# bms.net
KiCad netlist of a schematic drawn in EAGLE
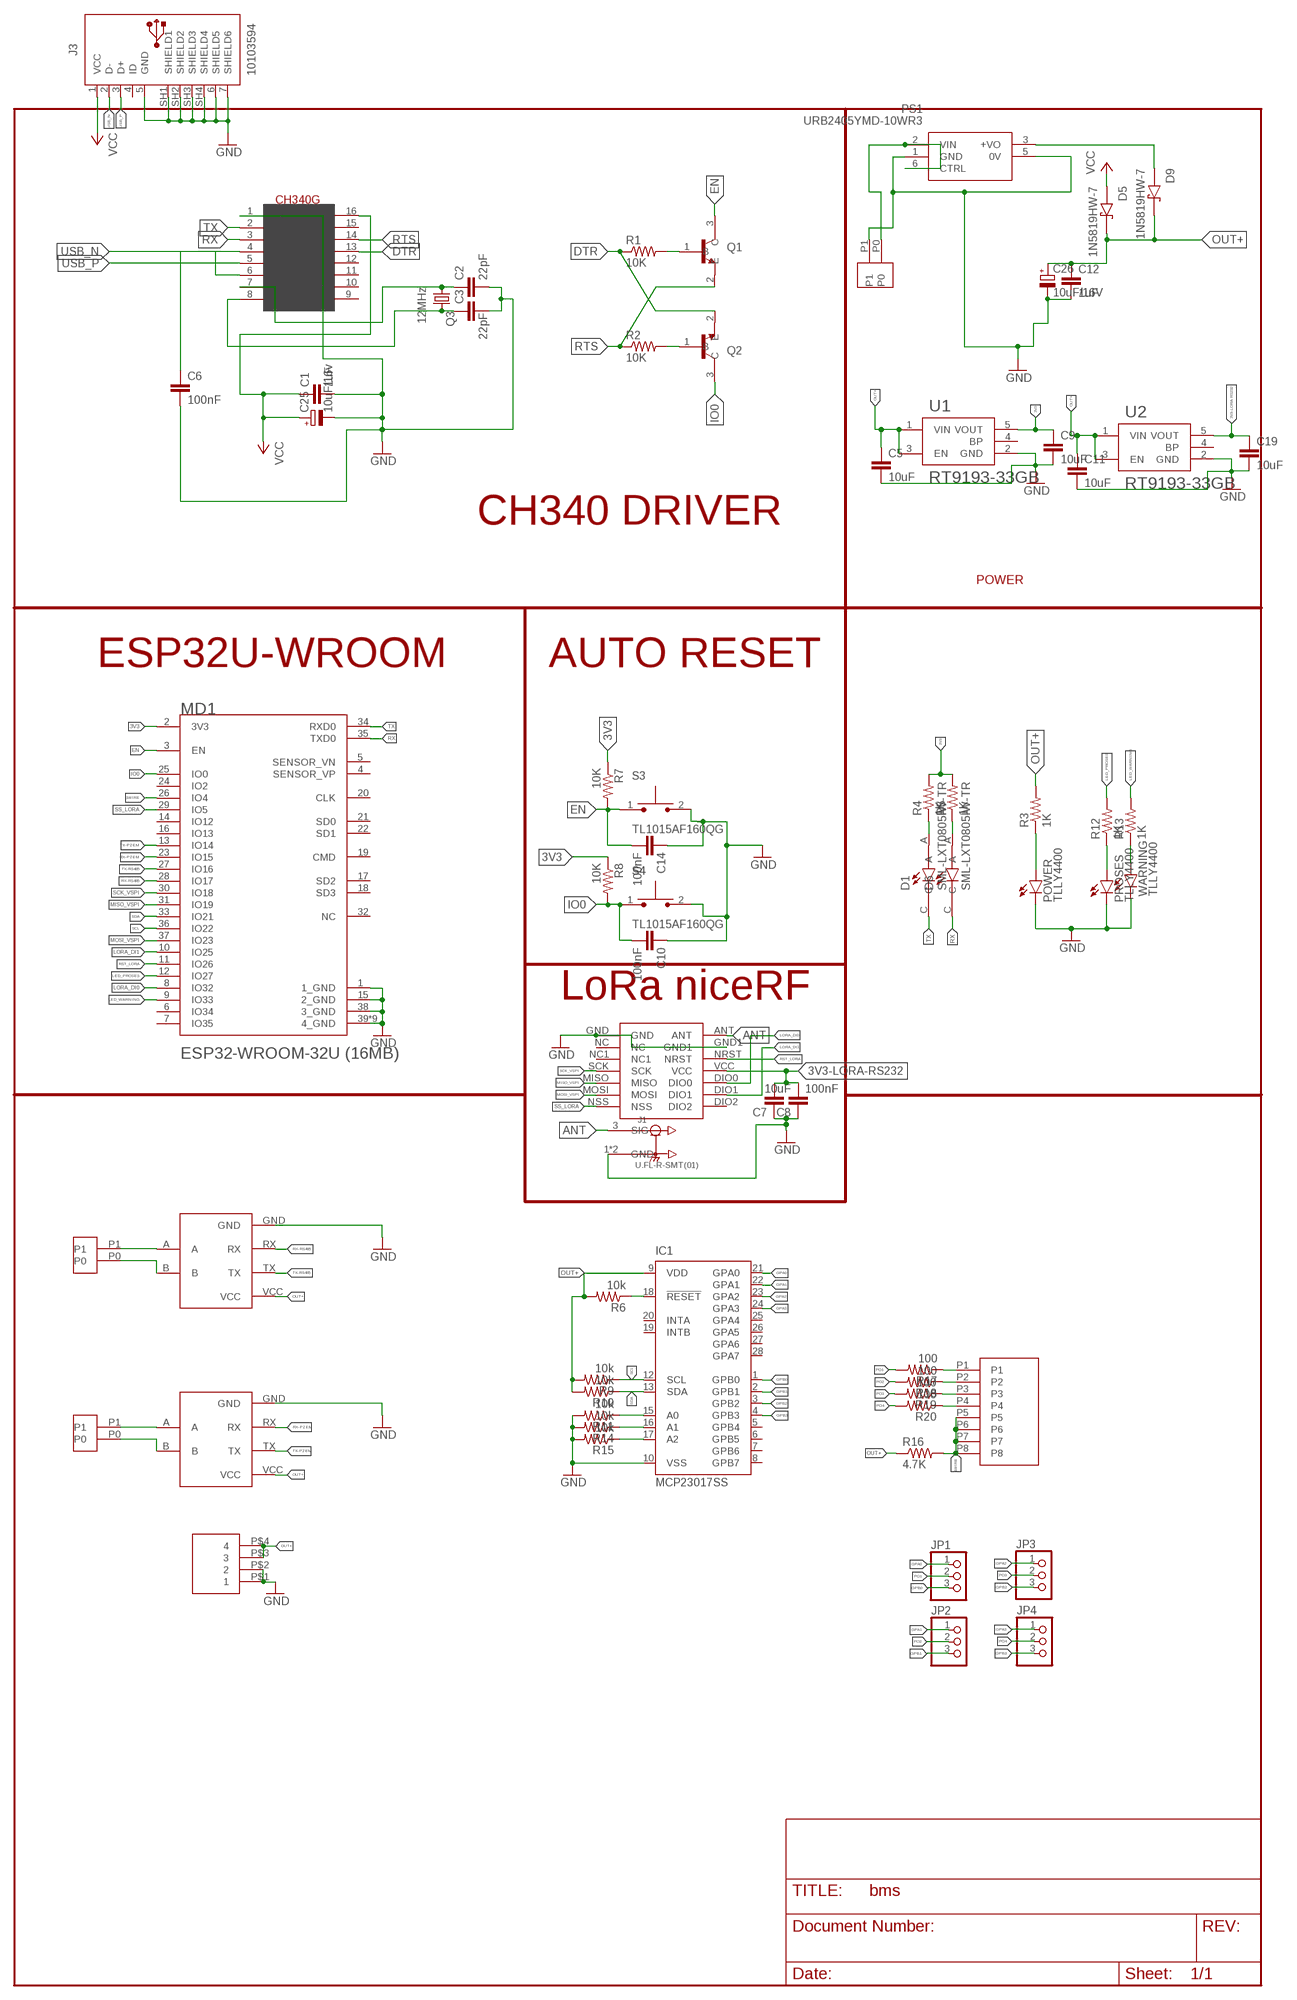
[diagram p0: schematic, sheet 1]

(export (version "E")
  (design (tool "Eeschema 10.0.6"))
  (components
    (comp (ref "C1")
      (value "1uF")
      (footprint "eagle-import:C0805K")
      (libsource (lib "eagle-import") (part "C-EUC0805K"))
    )
    (comp (ref "C2")
      (value "22pF")
      (footprint "eagle-import:C0805K")
      (libsource (lib "eagle-import") (part "C-EUC0805K"))
    )
    (comp (ref "C3")
      (value "22pF")
      (footprint "eagle-import:C0805K")
      (libsource (lib "eagle-import") (part "C-EUC0805K"))
    )
    (comp (ref "C5")
      (value "10uF")
      (footprint "eagle-import:C0805K")
      (libsource (lib "eagle-import") (part "C-EUC0805K"))
    )
    (comp (ref "C6")
      (value "100nF")
      (footprint "eagle-import:C0805K")
      (libsource (lib "eagle-import") (part "C-EUC0805K"))
    )
    (comp (ref "C7")
      (value "10uF")
      (footprint "eagle-import:C0805K")
      (libsource (lib "eagle-import") (part "C-EUC0805K"))
    )
    (comp (ref "C8")
      (value "100nF")
      (footprint "eagle-import:C0805K")
      (libsource (lib "eagle-import") (part "C-EUC0805K"))
    )
    (comp (ref "C9")
      (value "10uF")
      (footprint "eagle-import:C0805K")
      (libsource (lib "eagle-import") (part "C-EUC0805K"))
    )
    (comp (ref "C10")
      (value "100nF")
      (footprint "eagle-import:C0805K")
      (libsource (lib "eagle-import") (part "C-EUC0805K"))
    )
    (comp (ref "C11")
      (value "10uF")
      (footprint "eagle-import:C0805K")
      (libsource (lib "eagle-import") (part "C-EUC0805K"))
    )
    (comp (ref "C12")
      (value "1uF")
      (footprint "eagle-import:C0805K")
      (libsource (lib "eagle-import") (part "C-EUC0805K"))
    )
    (comp (ref "C14")
      (value "100nF")
      (footprint "eagle-import:C0805K")
      (libsource (lib "eagle-import") (part "C-EUC0805K"))
    )
    (comp (ref "C19")
      (value "10uF")
      (footprint "eagle-import:C0805K")
      (libsource (lib "eagle-import") (part "C-EUC0805K"))
    )
    (comp (ref "C25")
      (value "10uF/16v")
      (footprint "eagle-import:153CLV-0505")
      (libsource (lib "eagle-import") (part "CPOL-EU153CLV-0505"))
    )
    (comp (ref "C26")
      (value "10uF/16V")
      (footprint "eagle-import:153CLV-0505")
      (libsource (lib "eagle-import") (part "CPOL-EU153CLV-0505"))
    )
    (comp (ref "CONN2P-3.5PI1")
      (value "CONN2P-3.5PI")
      (footprint "eagle-import:CONN2P-3.5PI")
      (libsource (lib "eagle-import") (part "CONN2P-3.5PI"))
    )
    (comp (ref "CONN2P-3.5PI2")
      (value "CONN2P-3.5PI")
      (footprint "eagle-import:CONN2P-3.5PI")
      (libsource (lib "eagle-import") (part "CONN2P-3.5PI"))
    )
    (comp (ref "CONN2P-3.5PI3")
      (value "CONN2P-3.5PI")
      (footprint "eagle-import:CONN2P-3.5PI")
      (libsource (lib "eagle-import") (part "CONN2P-3.5PI"))
    )
    (comp (ref "CONN3.1")
      (value "CONN3.5")
      (footprint "eagle-import:CONN3.5")
      (libsource (lib "eagle-import") (part "CONN3.5"))
    )
    (comp (ref "D1")
      (value "SML-LXT0805IW-TR")
      (footprint "eagle-import:LEDC2012X120N")
      (fields (field (name "MF") "Lumex Opto/Components"))
      (libsource (lib "eagle-import") (part "SML-LXT0805IW-TR"))
    )
    (comp (ref "D5")
      (value "1N5819HW-7")
      (footprint "eagle-import:SOD3715X145N")
      (fields (field (name "MF") "Diodes Inc."))
      (libsource (lib "eagle-import") (part "1N5819HW-7"))
    )
    (comp (ref "D6")
      (value "SML-LXT0805IW-TR")
      (footprint "eagle-import:LEDC2012X120N")
      (fields (field (name "MF") "Lumex Opto/Components"))
      (libsource (lib "eagle-import") (part "SML-LXT0805IW-TR"))
    )
    (comp (ref "D9")
      (value "1N5819HW-7")
      (footprint "eagle-import:SOD3715X145N")
      (fields (field (name "MF") "Diodes Inc."))
      (libsource (lib "eagle-import") (part "1N5819HW-7"))
    )
    (comp (ref "HEADER-3.81-1")
      (value "HEADER-3.81-4")
      (footprint "eagle-import:HEADER-3.81-4")
      (libsource (lib "eagle-import") (part "HEADER-3.81-4"))
    )
    (comp (ref "IC1")
      (value "MCP23017SS")
      (footprint "eagle-import:SSOP28")
      (fields (field (name "MF") "MICROCHIP") (field (name "MPN") "MCP23017-E/SS"))
      (libsource (lib "eagle-import") (part "MCP23017SS"))
    )
    (comp (ref "J1")
      (value "U.FL-R-SMT(01)")
      (footprint "eagle-import:HRS_U.FL-R-SMT(01)")
      (fields (field (name "MF") "Hirose"))
      (libsource (lib "eagle-import") (part "U.FL-R-SMT(01)"))
    )
    (comp (ref "J3")
      (value "10103594")
      (footprint "eagle-import:10103594")
      (fields (field (name "MANUFACTURER") "Amphenol ICC (FCI)") (field (name "MPN") "10103594-0001LF"))
      (libsource (lib "eagle-import") (part "10103594"))
    )
    (comp (ref "JP1")
      (value "PINHD-1X3")
      (footprint "eagle-import:1X03")
      (libsource (lib "eagle-import") (part "PINHD-1X3"))
    )
    (comp (ref "JP2")
      (value "PINHD-1X3")
      (footprint "eagle-import:1X03")
      (libsource (lib "eagle-import") (part "PINHD-1X3"))
    )
    (comp (ref "JP3")
      (value "PINHD-1X3")
      (footprint "eagle-import:1X03")
      (libsource (lib "eagle-import") (part "PINHD-1X3"))
    )
    (comp (ref "JP4")
      (value "PINHD-1X3")
      (footprint "eagle-import:1X03")
      (libsource (lib "eagle-import") (part "PINHD-1X3"))
    )
    (comp (ref "LORA-NICERF-V1")
      (value "LORA-NICERF-V2")
      (footprint "eagle-import:LORA-NICERF-V2")
      (libsource (lib "eagle-import") (part "LORA-NICERF-V2"))
    )
    (comp (ref "MD1")
      (value "ESPRESSIF_SYSTEMS_ESP32-WROOM-32U_16MBESPRESSIF_SYSTEMS_ESP32-WROOM-32U_16MB_0_0")
      (footprint "eagle-import:ESPRESSIF_SYSTEMS_ESP32-WROOM-32U_16MB_0")
      (fields
        (field (name "DIGIKEY_PART_NUMBER") "1904-1028-1-ND")
        (field (name "MF") "Espressif Systems")
        (field (name "MOUSER_PART_NUMBER") "356-ES32WROOM32U16MB")
      )
      (libsource (lib "eagle-import") (part "ESPRESSIF_SYSTEMS_ESP32-WROOM-32U_16MBESPRESSIF_SYSTEMS_ESP32-WROOM-32U_16MB_0_0"))
    )
    (comp (ref "POWER")
      (value "TLLY4400")
      (footprint "eagle-import:LED3MM")
      (fields (field (name "MF") "VISHAY SEMICONDUCTOR"))
      (libsource (lib "eagle-import") (part "TLLY4400"))
    )
    (comp (ref "PROSES")
      (value "TLLY4400")
      (footprint "eagle-import:LED3MM")
      (fields (field (name "MF") "VISHAY SEMICONDUCTOR"))
      (libsource (lib "eagle-import") (part "TLLY4400"))
    )
    (comp (ref "PS1")
      (value "URB2405YMD-10WR3")
      (footprint "eagle-import:URB2405YMD10WR3")
      (libsource (lib "eagle-import") (part "URB2405YMD-10WR3"))
    )
    (comp (ref "Q1")
      (value "MMBT3904")
      (footprint "eagle-import:SOT95P240X120-3N")
      (fields (field (name "MF") "STMicroelectronics"))
      (libsource (lib "eagle-import") (part "MMBT3904"))
    )
    (comp (ref "Q2")
      (value "MMBT3904")
      (footprint "eagle-import:SOT95P240X120-3N")
      (fields (field (name "MF") "STMicroelectronics"))
      (libsource (lib "eagle-import") (part "MMBT3904"))
    )
    (comp (ref "Q3")
      (value "12MHz")
      (footprint "eagle-import:SM49")
      (libsource (lib "eagle-import") (part "CRYSTALSM49"))
    )
    (comp (ref "R1")
      (value "10K")
      (footprint "eagle-import:M0805")
      (libsource (lib "eagle-import") (part "R-US_M0805"))
    )
    (comp (ref "R2")
      (value "10K")
      (footprint "eagle-import:M0805")
      (libsource (lib "eagle-import") (part "R-US_M0805"))
    )
    (comp (ref "R3")
      (value "1K")
      (footprint "eagle-import:M0805")
      (libsource (lib "eagle-import") (part "R-US_M0805"))
    )
    (comp (ref "R4")
      (value "1K")
      (footprint "eagle-import:M0805")
      (libsource (lib "eagle-import") (part "R-US_M0805"))
    )
    (comp (ref "R5")
      (value "1K")
      (footprint "eagle-import:M0805")
      (libsource (lib "eagle-import") (part "R-US_M0805"))
    )
    (comp (ref "R6")
      (value "10k")
      (footprint "eagle-import:M0805")
      (libsource (lib "eagle-import") (part "R-US_M0805"))
    )
    (comp (ref "R7")
      (value "10K")
      (footprint "eagle-import:M0805")
      (libsource (lib "eagle-import") (part "R-US_M0805"))
    )
    (comp (ref "R8")
      (value "10K")
      (footprint "eagle-import:M0805")
      (libsource (lib "eagle-import") (part "R-US_M0805"))
    )
    (comp (ref "R9")
      (value "10k")
      (footprint "eagle-import:M0805")
      (libsource (lib "eagle-import") (part "R-US_M0805"))
    )
    (comp (ref "R10")
      (value "10k")
      (footprint "eagle-import:M0805")
      (libsource (lib "eagle-import") (part "R-US_M0805"))
    )
    (comp (ref "R11")
      (value "10k")
      (footprint "eagle-import:M0805")
      (libsource (lib "eagle-import") (part "R-US_M0805"))
    )
    (comp (ref "R12")
      (value "1K")
      (footprint "eagle-import:M0805")
      (libsource (lib "eagle-import") (part "R-US_M0805"))
    )
    (comp (ref "R13")
      (value "1K")
      (footprint "eagle-import:M0805")
      (libsource (lib "eagle-import") (part "R-US_M0805"))
    )
    (comp (ref "R14")
      (value "10k")
      (footprint "eagle-import:M0805")
      (libsource (lib "eagle-import") (part "R-US_M0805"))
    )
    (comp (ref "R15")
      (value "10k")
      (footprint "eagle-import:M0805")
      (libsource (lib "eagle-import") (part "R-US_M0805"))
    )
    (comp (ref "R16")
      (value "4.7K")
      (footprint "eagle-import:M0805")
      (libsource (lib "eagle-import") (part "R-US_M0805"))
    )
    (comp (ref "R17")
      (value "100")
      (footprint "eagle-import:M0805")
      (libsource (lib "eagle-import") (part "R-US_M0805"))
    )
    (comp (ref "R18")
      (value "100")
      (footprint "eagle-import:M0805")
      (libsource (lib "eagle-import") (part "R-US_M0805"))
    )
    (comp (ref "R19")
      (value "100")
      (footprint "eagle-import:M0805")
      (libsource (lib "eagle-import") (part "R-US_M0805"))
    )
    (comp (ref "R20")
      (value "100")
      (footprint "eagle-import:M0805")
      (libsource (lib "eagle-import") (part "R-US_M0805"))
    )
    (comp (ref "S3")
      (value "TL1015AF160QG")
      (footprint "eagle-import:SW_TL1015AF160QG")
      (fields (field (name "MF") "E-Switch"))
      (libsource (lib "eagle-import") (part "TL1015AF160QG"))
    )
    (comp (ref "S4")
      (value "TL1015AF160QG")
      (footprint "eagle-import:SW_TL1015AF160QG")
      (fields (field (name "MF") "E-Switch"))
      (libsource (lib "eagle-import") (part "TL1015AF160QG"))
    )
    (comp (ref "TTL-RS1")
      (value "TTL-RS485")
      (footprint "eagle-import:TTL-RS485")
      (libsource (lib "eagle-import") (part "TTL-RS485"))
    )
    (comp (ref "TTL-RS2")
      (value "TTL-RS485")
      (footprint "eagle-import:TTL-RS485")
      (libsource (lib "eagle-import") (part "TTL-RS485"))
    )
    (comp (ref "U$2")
      (value "CH340G")
      (footprint "eagle-import:SOIC16")
      (libsource (lib "eagle-import") (part "CH340G"))
    )
    (comp (ref "U1")
      (value "RT9193-33GB")
      (footprint "eagle-import:SOT94P279X129-5N")
      (fields (field (name "MF") "Richtek USA Inc."))
      (libsource (lib "eagle-import") (part "RT9193-33GB"))
    )
    (comp (ref "U2")
      (value "RT9193-33GB")
      (footprint "eagle-import:SOT94P279X129-5N")
      (fields (field (name "MF") "Richtek USA Inc."))
      (libsource (lib "eagle-import") (part "RT9193-33GB"))
    )
    (comp (ref "WARNING")
      (value "TLLY4400")
      (footprint "eagle-import:LED3MM")
      (fields (field (name "MF") "VISHAY SEMICONDUCTOR"))
      (libsource (lib "eagle-import") (part "TLLY4400"))
    )
  )
  (nets
    (net (code "1") (name "1WIRE") (class "Default")
      (node (ref "CONN3.1") (pin "P5") (pinfunction "P5_P5") (pintype "bidirectional"))
      (node (ref "CONN3.1") (pin "P6") (pinfunction "P6_P6") (pintype "bidirectional"))
      (node (ref "CONN3.1") (pin "P7") (pinfunction "P7_P7") (pintype "bidirectional"))
      (node (ref "CONN3.1") (pin "P8") (pinfunction "P8_P8") (pintype "bidirectional"))
      (node (ref "MD1") (pin "26") (pinfunction "IO4_26") (pintype "bidirectional"))
      (node (ref "R16") (pin "2") (pinfunction "2_2") (pintype "passive"))
    )
    (net (code "2") (name "3V3") (class "Default")
      (node (ref "C9") (pin "1") (pinfunction "1_1") (pintype "passive"))
      (node (ref "MD1") (pin "2") (pinfunction "3V3_2") (pintype "power_in"))
      (node (ref "R4") (pin "2") (pinfunction "2_2") (pintype "passive"))
      (node (ref "R5") (pin "2") (pinfunction "2_2") (pintype "passive"))
      (node (ref "R7") (pin "1") (pinfunction "1_1") (pintype "passive"))
      (node (ref "R8") (pin "1") (pinfunction "1_1") (pintype "passive"))
      (node (ref "U1") (pin "5") (pinfunction "VOUT_5") (pintype "output"))
    )
    (net (code "3") (name "3V3-LORA-RS232") (class "Default")
      (node (ref "C19") (pin "1") (pinfunction "1_1") (pintype "passive"))
      (node (ref "C7") (pin "2") (pinfunction "2_2") (pintype "passive"))
      (node (ref "C8") (pin "2") (pinfunction "2_2") (pintype "passive"))
      (node (ref "LORA-NICERF-V1") (pin "VCC") (pinfunction "VCC_VCC") (pintype "bidirectional"))
      (node (ref "U2") (pin "5") (pinfunction "VOUT_5") (pintype "output"))
    )
    (net (code "4") (name "ANT") (class "Default")
      (node (ref "J1") (pin "3") (pinfunction "SIG_3") (pintype "passive"))
      (node (ref "LORA-NICERF-V1") (pin "ANT") (pinfunction "ANT_ANT") (pintype "bidirectional"))
    )
    (net (code "5") (name "DTR") (class "Default")
      (node (ref "Q2") (pin "2") (pinfunction "E_2") (pintype "passive"))
      (node (ref "R1") (pin "1") (pinfunction "1_1") (pintype "passive"))
      (node (ref "U$2") (pin "13") (pinfunction "DTR_13") (pintype "bidirectional"))
    )
    (net (code "6") (name "EN") (class "Default")
      (node (ref "C14") (pin "2") (pinfunction "2_2") (pintype "passive"))
      (node (ref "MD1") (pin "3") (pinfunction "EN_3") (pintype "input"))
      (node (ref "Q1") (pin "3") (pinfunction "C_3") (pintype "passive"))
      (node (ref "R7") (pin "2") (pinfunction "2_2") (pintype "passive"))
      (node (ref "S3") (pin "1") (pinfunction "1_1") (pintype "passive"))
    )
    (net (code "7") (name "GND") (class "Default")
      (node (ref "C1") (pin "2") (pinfunction "2_2") (pintype "passive"))
      (node (ref "C10") (pin "1") (pinfunction "1_1") (pintype "passive"))
      (node (ref "C11") (pin "2") (pinfunction "2_2") (pintype "passive"))
      (node (ref "C12") (pin "2") (pinfunction "2_2") (pintype "passive"))
      (node (ref "C14") (pin "1") (pinfunction "1_1") (pintype "passive"))
      (node (ref "C19") (pin "2") (pinfunction "2_2") (pintype "passive"))
      (node (ref "C2") (pin "2") (pinfunction "2_2") (pintype "passive"))
      (node (ref "C25") (pin "-") (pinfunction "-_-") (pintype "passive"))
      (node (ref "C26") (pin "-") (pinfunction "-_-") (pintype "passive"))
      (node (ref "C3") (pin "2") (pinfunction "2_2") (pintype "passive"))
      (node (ref "C5") (pin "2") (pinfunction "2_2") (pintype "passive"))
      (node (ref "C6") (pin "2") (pinfunction "2_2") (pintype "passive"))
      (node (ref "C7") (pin "1") (pinfunction "1_1") (pintype "passive"))
      (node (ref "C8") (pin "1") (pinfunction "1_1") (pintype "passive"))
      (node (ref "C9") (pin "2") (pinfunction "2_2") (pintype "passive"))
      (node (ref "CONN2P-3.5PI1") (pin "P1") (pinfunction "P1_P1") (pintype "bidirectional"))
      (node (ref "HEADER-3.81-1") (pin "P$1") (pinfunction "1_P$1") (pintype "bidirectional"))
      (node (ref "HEADER-3.81-1") (pin "P$2") (pinfunction "2_P$2") (pintype "bidirectional"))
      (node (ref "IC1") (pin "10") (pinfunction "VSS_10") (pintype "power_in"))
      (node (ref "J1") (pin "1") (pinfunction "GND_1") (pintype "passive"))
      (node (ref "J1") (pin "2") (pinfunction "GND_2") (pintype "passive"))
      (node (ref "J3") (pin "5") (pinfunction "GND_5") (pintype "power_in"))
      (node (ref "J3") (pin "6") (pinfunction "SHIELD5_6") (pintype "power_in"))
      (node (ref "J3") (pin "7") (pinfunction "SHIELD6_7") (pintype "power_in"))
      (node (ref "J3") (pin "SH1") (pinfunction "SHIELD1_SH1") (pintype "power_in"))
      (node (ref "J3") (pin "SH2") (pinfunction "SHIELD2_SH2") (pintype "power_in"))
      (node (ref "J3") (pin "SH3") (pinfunction "SHIELD3_SH3") (pintype "power_in"))
      (node (ref "J3") (pin "SH4") (pinfunction "SHIELD4_SH4") (pintype "power_in"))
      (node (ref "LORA-NICERF-V1") (pin "GND") (pinfunction "GND_GND") (pintype "bidirectional"))
      (node (ref "LORA-NICERF-V1") (pin "GND1") (pinfunction "GND1_GND1") (pintype "bidirectional"))
      (node (ref "MD1") (pin "1") (pinfunction "1_GND_1") (pintype "power_in"))
      (node (ref "MD1") (pin "15") (pinfunction "2_GND_15") (pintype "power_in"))
      (node (ref "MD1") (pin "38") (pinfunction "3_GND_38") (pintype "power_in"))
      (node (ref "MD1") (pin "39") (pinfunction "4_GND_39") (pintype "power_in"))
      (node (ref "MD1") (pin "39-2") (pinfunction "4_GND_39-2") (pintype "power_in"))
      (node (ref "MD1") (pin "39-3") (pinfunction "4_GND_39-3") (pintype "power_in"))
      (node (ref "MD1") (pin "39-4") (pinfunction "4_GND_39-4") (pintype "power_in"))
      (node (ref "MD1") (pin "39-5") (pinfunction "4_GND_39-5") (pintype "power_in"))
      (node (ref "MD1") (pin "39-6") (pinfunction "4_GND_39-6") (pintype "power_in"))
      (node (ref "MD1") (pin "39-7") (pinfunction "4_GND_39-7") (pintype "power_in"))
      (node (ref "MD1") (pin "39-8") (pinfunction "4_GND_39-8") (pintype "power_in"))
      (node (ref "MD1") (pin "39-9") (pinfunction "4_GND_39-9") (pintype "power_in"))
      (node (ref "POWER") (pin "K") (pinfunction "C_K") (pintype "passive"))
      (node (ref "PROSES") (pin "K") (pinfunction "C_K") (pintype "passive"))
      (node (ref "PS1") (pin "1") (pinfunction "GND_1") (pintype "bidirectional"))
      (node (ref "PS1") (pin "5") (pinfunction "0V_5") (pintype "bidirectional"))
      (node (ref "R11") (pin "2") (pinfunction "2_2") (pintype "passive"))
      (node (ref "R14") (pin "2") (pinfunction "2_2") (pintype "passive"))
      (node (ref "R15") (pin "2") (pinfunction "2_2") (pintype "passive"))
      (node (ref "S3") (pin "2") (pinfunction "2_2") (pintype "passive"))
      (node (ref "S4") (pin "2") (pinfunction "2_2") (pintype "passive"))
      (node (ref "TTL-RS1") (pin "GND") (pinfunction "GND_GND") (pintype "bidirectional"))
      (node (ref "TTL-RS2") (pin "GND") (pinfunction "GND_GND") (pintype "bidirectional"))
      (node (ref "U$2") (pin "1") (pinfunction "GND_1") (pintype "bidirectional"))
      (node (ref "U1") (pin "2") (pinfunction "GND_2") (pintype "power_in"))
      (node (ref "U2") (pin "2") (pinfunction "GND_2") (pintype "power_in"))
      (node (ref "WARNING") (pin "K") (pinfunction "C_K") (pintype "passive"))
    )
    (net (code "8") (name "GPA0") (class "Default")
      (node (ref "IC1") (pin "21") (pinfunction "GPA0_21") (pintype "bidirectional"))
      (node (ref "JP1") (pin "1") (pinfunction "1_1") (pintype "passive"))
    )
    (net (code "9") (name "GPA1") (class "Default")
      (node (ref "IC1") (pin "22") (pinfunction "GPA1_22") (pintype "bidirectional"))
      (node (ref "JP2") (pin "1") (pinfunction "1_1") (pintype "passive"))
    )
    (net (code "10") (name "GPA2") (class "Default")
      (node (ref "IC1") (pin "23") (pinfunction "GPA2_23") (pintype "bidirectional"))
      (node (ref "JP3") (pin "1") (pinfunction "1_1") (pintype "passive"))
    )
    (net (code "11") (name "GPA3") (class "Default")
      (node (ref "IC1") (pin "24") (pinfunction "GPA3_24") (pintype "bidirectional"))
      (node (ref "JP4") (pin "1") (pinfunction "1_1") (pintype "passive"))
    )
    (net (code "12") (name "GPB0") (class "Default")
      (node (ref "IC1") (pin "1") (pinfunction "GPB0_1") (pintype "bidirectional"))
      (node (ref "JP1") (pin "3") (pinfunction "3_3") (pintype "passive"))
    )
    (net (code "13") (name "GPB1") (class "Default")
      (node (ref "IC1") (pin "2") (pinfunction "GPB1_2") (pintype "bidirectional"))
      (node (ref "JP2") (pin "3") (pinfunction "3_3") (pintype "passive"))
    )
    (net (code "14") (name "GPB2") (class "Default")
      (node (ref "IC1") (pin "3") (pinfunction "GPB2_3") (pintype "bidirectional"))
      (node (ref "JP3") (pin "3") (pinfunction "3_3") (pintype "passive"))
    )
    (net (code "15") (name "GPB3") (class "Default")
      (node (ref "IC1") (pin "4") (pinfunction "GPB3_4") (pintype "bidirectional"))
      (node (ref "JP4") (pin "3") (pinfunction "3_3") (pintype "passive"))
    )
    (net (code "16") (name "IO0") (class "Default")
      (node (ref "C10") (pin "2") (pinfunction "2_2") (pintype "passive"))
      (node (ref "MD1") (pin "25") (pinfunction "IO0_25") (pintype "bidirectional"))
      (node (ref "Q2") (pin "3") (pinfunction "C_3") (pintype "passive"))
      (node (ref "R8") (pin "2") (pinfunction "2_2") (pintype "passive"))
      (node (ref "S4") (pin "1") (pinfunction "1_1") (pintype "passive"))
    )
    (net (code "17") (name "LED_PROSES") (class "Default")
      (node (ref "MD1") (pin "12") (pinfunction "IO27_12") (pintype "bidirectional"))
      (node (ref "R12") (pin "2") (pinfunction "2_2") (pintype "passive"))
    )
    (net (code "18") (name "LED_WARNING") (class "Default")
      (node (ref "MD1") (pin "9") (pinfunction "IO33_9") (pintype "bidirectional"))
      (node (ref "R13") (pin "2") (pinfunction "2_2") (pintype "passive"))
    )
    (net (code "19") (name "LORA_DI0") (class "Default")
      (node (ref "LORA-NICERF-V1") (pin "DIO0") (pinfunction "DIO0_DIO0") (pintype "bidirectional"))
      (node (ref "MD1") (pin "8") (pinfunction "IO32_8") (pintype "bidirectional"))
    )
    (net (code "20") (name "LORA_DI1") (class "Default")
      (node (ref "LORA-NICERF-V1") (pin "DIO1") (pinfunction "DIO1_DIO1") (pintype "bidirectional"))
      (node (ref "MD1") (pin "10") (pinfunction "IO25_10") (pintype "bidirectional"))
    )
    (net (code "21") (name "MISO_VSPI") (class "Default")
      (node (ref "LORA-NICERF-V1") (pin "MISO") (pinfunction "MISO_MISO") (pintype "bidirectional"))
      (node (ref "MD1") (pin "31") (pinfunction "IO19_31") (pintype "bidirectional"))
    )
    (net (code "22") (name "MOSI_VSPI") (class "Default")
      (node (ref "LORA-NICERF-V1") (pin "MOSI") (pinfunction "MOSI_MOSI") (pintype "bidirectional"))
      (node (ref "MD1") (pin "37") (pinfunction "IO23_37") (pintype "bidirectional"))
    )
    (net (code "23") (name "Net-(CONN2P-3.5PI2-PadP0)") (class "Default")
      (node (ref "CONN2P-3.5PI2") (pin "P0") (pinfunction "P0_P0") (pintype "bidirectional"))
      (node (ref "TTL-RS1") (pin "B") (pinfunction "B_B") (pintype "bidirectional"))
    )
    (net (code "24") (name "Net-(CONN2P-3.5PI2-PadP1)") (class "Default")
      (node (ref "CONN2P-3.5PI2") (pin "P1") (pinfunction "P1_P1") (pintype "bidirectional"))
      (node (ref "TTL-RS1") (pin "A") (pinfunction "A_A") (pintype "bidirectional"))
    )
    (net (code "25") (name "Net-(CONN2P-3.5PI3-PadP0)") (class "Default")
      (node (ref "CONN2P-3.5PI3") (pin "P0") (pinfunction "P0_P0") (pintype "bidirectional"))
      (node (ref "TTL-RS2") (pin "B") (pinfunction "B_B") (pintype "bidirectional"))
    )
    (net (code "26") (name "Net-(CONN2P-3.5PI3-PadP1)") (class "Default")
      (node (ref "CONN2P-3.5PI3") (pin "P1") (pinfunction "P1_P1") (pintype "bidirectional"))
      (node (ref "TTL-RS2") (pin "A") (pinfunction "A_A") (pintype "bidirectional"))
    )
    (net (code "27") (name "Net-(CONN3.1-PadP1)") (class "Default")
      (node (ref "CONN3.1") (pin "P1") (pinfunction "P1_P1") (pintype "bidirectional"))
      (node (ref "R17") (pin "1") (pinfunction "1_1") (pintype "passive"))
    )
    (net (code "28") (name "Net-(CONN3.1-PadP2)") (class "Default")
      (node (ref "CONN3.1") (pin "P2") (pinfunction "P2_P2") (pintype "bidirectional"))
      (node (ref "R18") (pin "1") (pinfunction "1_1") (pintype "passive"))
    )
    (net (code "29") (name "Net-(CONN3.1-PadP3)") (class "Default")
      (node (ref "CONN3.1") (pin "P3") (pinfunction "P3_P3") (pintype "bidirectional"))
      (node (ref "R19") (pin "1") (pinfunction "1_1") (pintype "passive"))
    )
    (net (code "30") (name "Net-(CONN3.1-PadP4)") (class "Default")
      (node (ref "CONN3.1") (pin "P4") (pinfunction "P4_P4") (pintype "bidirectional"))
      (node (ref "R20") (pin "1") (pinfunction "1_1") (pintype "passive"))
    )
    (net (code "31") (name "Net-(D1-PadA)") (class "Default")
      (node (ref "D1") (pin "A") (pinfunction "A_A") (pintype "passive"))
      (node (ref "R4") (pin "1") (pinfunction "1_1") (pintype "passive"))
    )
    (net (code "32") (name "Net-(D6-PadA)") (class "Default")
      (node (ref "D6") (pin "A") (pinfunction "A_A") (pintype "passive"))
      (node (ref "R5") (pin "1") (pinfunction "1_1") (pintype "passive"))
    )
    (net (code "33") (name "Net-(IC1-A0)") (class "Default")
      (node (ref "IC1") (pin "15") (pinfunction "A0_15") (pintype "input"))
      (node (ref "R11") (pin "1") (pinfunction "1_1") (pintype "passive"))
    )
    (net (code "34") (name "Net-(IC1-A1)") (class "Default")
      (node (ref "IC1") (pin "16") (pinfunction "A1_16") (pintype "input"))
      (node (ref "R14") (pin "1") (pinfunction "1_1") (pintype "passive"))
    )
    (net (code "35") (name "Net-(IC1-A2)") (class "Default")
      (node (ref "IC1") (pin "17") (pinfunction "A2_17") (pintype "input"))
      (node (ref "R15") (pin "1") (pinfunction "1_1") (pintype "passive"))
    )
    (net (code "36") (name "Net-(IC1-~{RESET})") (class "Default")
      (node (ref "IC1") (pin "18") (pinfunction "~{RESET}_18") (pintype "input"))
      (node (ref "R6") (pin "1") (pinfunction "1_1") (pintype "passive"))
    )
    (net (code "37") (name "Net-(POWER-PadA)") (class "Default")
      (node (ref "POWER") (pin "A") (pinfunction "A_A") (pintype "passive"))
      (node (ref "R3") (pin "1") (pinfunction "1_1") (pintype "passive"))
    )
    (net (code "38") (name "Net-(PROSES-PadA)") (class "Default")
      (node (ref "PROSES") (pin "A") (pinfunction "A_A") (pintype "passive"))
      (node (ref "R12") (pin "1") (pinfunction "1_1") (pintype "passive"))
    )
    (net (code "39") (name "Net-(PS1-+VO)") (class "Default")
      (node (ref "D9") (pin "A") (pinfunction "A_A") (pintype "passive"))
      (node (ref "PS1") (pin "3") (pinfunction "+VO_3") (pintype "bidirectional"))
    )
    (net (code "40") (name "Net-(PS1-CTRL)") (class "Default")
      (node (ref "CONN2P-3.5PI1") (pin "P0") (pinfunction "P0_P0") (pintype "bidirectional"))
      (node (ref "PS1") (pin "2") (pinfunction "VIN_2") (pintype "bidirectional"))
      (node (ref "PS1") (pin "6") (pinfunction "CTRL_6") (pintype "bidirectional"))
    )
    (net (code "41") (name "Net-(Q1-B)") (class "Default")
      (node (ref "Q1") (pin "1") (pinfunction "B_1") (pintype "passive"))
      (node (ref "R1") (pin "2") (pinfunction "2_2") (pintype "passive"))
    )
    (net (code "42") (name "Net-(Q2-B)") (class "Default")
      (node (ref "Q2") (pin "1") (pinfunction "B_1") (pintype "passive"))
      (node (ref "R2") (pin "2") (pinfunction "2_2") (pintype "passive"))
    )
    (net (code "43") (name "Net-(R13-Pad1)") (class "Default")
      (node (ref "R13") (pin "1") (pinfunction "1_1") (pintype "passive"))
      (node (ref "WARNING") (pin "A") (pinfunction "A_A") (pintype "passive"))
    )
    (net (code "44") (name "Net-(U$2-V3)") (class "Default")
      (node (ref "C6") (pin "1") (pinfunction "1_1") (pintype "passive"))
      (node (ref "U$2") (pin "4") (pinfunction "V3_4") (pintype "bidirectional"))
    )
    (net (code "45") (name "Net-(U$2-XI)") (class "Default")
      (node (ref "C2") (pin "1") (pinfunction "1_1") (pintype "passive"))
      (node (ref "Q3") (pin "1") (pinfunction "1_1") (pintype "passive"))
      (node (ref "U$2") (pin "7") (pinfunction "XI_7") (pintype "bidirectional"))
    )
    (net (code "46") (name "Net-(U$2-XO)") (class "Default")
      (node (ref "C3") (pin "1") (pinfunction "1_1") (pintype "passive"))
      (node (ref "Q3") (pin "2") (pinfunction "2_2") (pintype "passive"))
      (node (ref "U$2") (pin "8") (pinfunction "XO_8") (pintype "bidirectional"))
    )
    (net (code "47") (name "OUT+") (class "Default")
      (node (ref "C11") (pin "1") (pinfunction "1_1") (pintype "passive"))
      (node (ref "C12") (pin "1") (pinfunction "1_1") (pintype "passive"))
      (node (ref "C26") (pin "+") (pinfunction "+_+") (pintype "passive"))
      (node (ref "C5") (pin "1") (pinfunction "1_1") (pintype "passive"))
      (node (ref "D5") (pin "C") (pinfunction "K_C") (pintype "passive"))
      (node (ref "D9") (pin "C") (pinfunction "K_C") (pintype "passive"))
      (node (ref "HEADER-3.81-1") (pin "P$3") (pinfunction "3_P$3") (pintype "bidirectional"))
      (node (ref "HEADER-3.81-1") (pin "P$4") (pinfunction "4_P$4") (pintype "bidirectional"))
      (node (ref "IC1") (pin "9") (pinfunction "VDD_9") (pintype "power_in"))
      (node (ref "R10") (pin "2") (pinfunction "2_2") (pintype "passive"))
      (node (ref "R16") (pin "1") (pinfunction "1_1") (pintype "passive"))
      (node (ref "R3") (pin "2") (pinfunction "2_2") (pintype "passive"))
      (node (ref "R6") (pin "2") (pinfunction "2_2") (pintype "passive"))
      (node (ref "R9") (pin "2") (pinfunction "2_2") (pintype "passive"))
      (node (ref "TTL-RS1") (pin "VCC") (pinfunction "VCC_VCC") (pintype "bidirectional"))
      (node (ref "TTL-RS2") (pin "VCC") (pinfunction "VCC_VCC") (pintype "bidirectional"))
      (node (ref "U1") (pin "1") (pinfunction "VIN_1") (pintype "input"))
      (node (ref "U1") (pin "3") (pinfunction "EN_3") (pintype "input"))
      (node (ref "U2") (pin "1") (pinfunction "VIN_1") (pintype "input"))
      (node (ref "U2") (pin "3") (pinfunction "EN_3") (pintype "input"))
    )
    (net (code "48") (name "PO1") (class "Default")
      (node (ref "JP1") (pin "2") (pinfunction "2_2") (pintype "passive"))
      (node (ref "R17") (pin "2") (pinfunction "2_2") (pintype "passive"))
    )
    (net (code "49") (name "PO2") (class "Default")
      (node (ref "JP2") (pin "2") (pinfunction "2_2") (pintype "passive"))
      (node (ref "R18") (pin "2") (pinfunction "2_2") (pintype "passive"))
    )
    (net (code "50") (name "PO3") (class "Default")
      (node (ref "JP3") (pin "2") (pinfunction "2_2") (pintype "passive"))
      (node (ref "R19") (pin "2") (pinfunction "2_2") (pintype "passive"))
    )
    (net (code "51") (name "PO4") (class "Default")
      (node (ref "JP4") (pin "2") (pinfunction "2_2") (pintype "passive"))
      (node (ref "R20") (pin "2") (pinfunction "2_2") (pintype "passive"))
    )
    (net (code "52") (name "RST_LORA") (class "Default")
      (node (ref "LORA-NICERF-V1") (pin "NRST") (pinfunction "NRST_NRST") (pintype "bidirectional"))
      (node (ref "MD1") (pin "11") (pinfunction "IO26_11") (pintype "bidirectional"))
    )
    (net (code "53") (name "RTS") (class "Default")
      (node (ref "Q1") (pin "2") (pinfunction "E_2") (pintype "passive"))
      (node (ref "R2") (pin "1") (pinfunction "1_1") (pintype "passive"))
      (node (ref "U$2") (pin "14") (pinfunction "RTS_14") (pintype "bidirectional"))
    )
    (net (code "54") (name "RX") (class "Default")
      (node (ref "D6") (pin "C") (pinfunction "C_C") (pintype "passive"))
      (node (ref "MD1") (pin "35") (pinfunction "TXD0_35") (pintype "bidirectional"))
      (node (ref "U$2") (pin "3") (pinfunction "RX_3") (pintype "bidirectional"))
    )
    (net (code "55") (name "RX-PZEM") (class "Default")
      (node (ref "MD1") (pin "23") (pinfunction "IO15_23") (pintype "bidirectional"))
      (node (ref "TTL-RS2") (pin "RX") (pinfunction "RX_RX") (pintype "bidirectional"))
    )
    (net (code "56") (name "RX-RS485") (class "Default")
      (node (ref "MD1") (pin "28") (pinfunction "IO17_28") (pintype "bidirectional"))
      (node (ref "TTL-RS1") (pin "RX") (pinfunction "RX_RX") (pintype "bidirectional"))
    )
    (net (code "57") (name "SCK_VSPI") (class "Default")
      (node (ref "LORA-NICERF-V1") (pin "SCK") (pinfunction "SCK_SCK") (pintype "bidirectional"))
      (node (ref "MD1") (pin "30") (pinfunction "IO18_30") (pintype "bidirectional"))
    )
    (net (code "58") (name "SCL") (class "Default")
      (node (ref "IC1") (pin "12") (pinfunction "SCL_12") (pintype "input"))
      (node (ref "MD1") (pin "36") (pinfunction "IO22_36") (pintype "bidirectional"))
      (node (ref "R9") (pin "1") (pinfunction "1_1") (pintype "passive"))
    )
    (net (code "59") (name "SDA") (class "Default")
      (node (ref "IC1") (pin "13") (pinfunction "SDA_13") (pintype "bidirectional"))
      (node (ref "MD1") (pin "33") (pinfunction "IO21_33") (pintype "bidirectional"))
      (node (ref "R10") (pin "1") (pinfunction "1_1") (pintype "passive"))
    )
    (net (code "60") (name "SS_LORA") (class "Default")
      (node (ref "LORA-NICERF-V1") (pin "NSS") (pinfunction "NSS_NSS") (pintype "bidirectional"))
      (node (ref "MD1") (pin "29") (pinfunction "IO5_29") (pintype "bidirectional"))
    )
    (net (code "61") (name "TX") (class "Default")
      (node (ref "D1") (pin "C") (pinfunction "C_C") (pintype "passive"))
      (node (ref "MD1") (pin "34") (pinfunction "RXD0_34") (pintype "bidirectional"))
      (node (ref "U$2") (pin "2") (pinfunction "TX_2") (pintype "bidirectional"))
    )
    (net (code "62") (name "TX-PZEM") (class "Default")
      (node (ref "MD1") (pin "13") (pinfunction "IO14_13") (pintype "bidirectional"))
      (node (ref "TTL-RS2") (pin "TX") (pinfunction "TX_TX") (pintype "bidirectional"))
    )
    (net (code "63") (name "TX-RS485") (class "Default")
      (node (ref "MD1") (pin "27") (pinfunction "IO16_27") (pintype "bidirectional"))
      (node (ref "TTL-RS1") (pin "TX") (pinfunction "TX_TX") (pintype "bidirectional"))
    )
    (net (code "64") (name "USB_N") (class "Default")
      (node (ref "J3") (pin "2") (pinfunction "D-_2") (pintype "bidirectional"))
      (node (ref "U$2") (pin "6") (pinfunction "D-_6") (pintype "bidirectional"))
    )
    (net (code "65") (name "USB_P") (class "Default")
      (node (ref "J3") (pin "3") (pinfunction "D+_3") (pintype "bidirectional"))
      (node (ref "U$2") (pin "5") (pinfunction "D+_5") (pintype "bidirectional"))
    )
    (net (code "66") (name "VCC") (class "Default")
      (node (ref "C1") (pin "1") (pinfunction "1_1") (pintype "passive"))
      (node (ref "C25") (pin "+") (pinfunction "+_+") (pintype "passive"))
      (node (ref "D5") (pin "A") (pinfunction "A_A") (pintype "passive"))
      (node (ref "J3") (pin "1") (pinfunction "VCC_1") (pintype "power_in"))
      (node (ref "U$2") (pin "16") (pinfunction "VCC_16") (pintype "bidirectional"))
    )
    (net (code "67") (name "unconnected-(IC1-GPA4-Pad25)") (class "Default")
      (node (ref "IC1") (pin "25") (pinfunction "GPA4_25") (pintype "bidirectional"))
    )
    (net (code "68") (name "unconnected-(IC1-GPA5-Pad26)") (class "Default")
      (node (ref "IC1") (pin "26") (pinfunction "GPA5_26") (pintype "bidirectional"))
    )
    (net (code "69") (name "unconnected-(IC1-GPA6-Pad27)") (class "Default")
      (node (ref "IC1") (pin "27") (pinfunction "GPA6_27") (pintype "bidirectional"))
    )
    (net (code "70") (name "unconnected-(IC1-GPA7-Pad28)") (class "Default")
      (node (ref "IC1") (pin "28") (pinfunction "GPA7_28") (pintype "bidirectional"))
    )
    (net (code "71") (name "unconnected-(IC1-GPB4-Pad5)") (class "Default")
      (node (ref "IC1") (pin "5") (pinfunction "GPB4_5") (pintype "bidirectional"))
    )
    (net (code "72") (name "unconnected-(IC1-GPB5-Pad6)") (class "Default")
      (node (ref "IC1") (pin "6") (pinfunction "GPB5_6") (pintype "bidirectional"))
    )
    (net (code "73") (name "unconnected-(IC1-GPB6-Pad7)") (class "Default")
      (node (ref "IC1") (pin "7") (pinfunction "GPB6_7") (pintype "bidirectional"))
    )
    (net (code "74") (name "unconnected-(IC1-GPB7-Pad8)") (class "Default")
      (node (ref "IC1") (pin "8") (pinfunction "GPB7_8") (pintype "bidirectional"))
    )
    (net (code "75") (name "unconnected-(IC1-INTA-Pad20)") (class "Default")
      (node (ref "IC1") (pin "20") (pinfunction "INTA_20") (pintype "output"))
    )
    (net (code "76") (name "unconnected-(IC1-INTB-Pad19)") (class "Default")
      (node (ref "IC1") (pin "19") (pinfunction "INTB_19") (pintype "output"))
    )
    (net (code "77") (name "unconnected-(J3-ID-Pad4)") (class "Default")
      (node (ref "J3") (pin "4") (pinfunction "ID_4") (pintype "bidirectional"))
    )
    (net (code "78") (name "unconnected-(LORA-NICERF-V1-PadDIO2)") (class "Default")
      (node (ref "LORA-NICERF-V1") (pin "DIO2") (pinfunction "DIO2_DIO2") (pintype "bidirectional"))
    )
    (net (code "79") (name "unconnected-(LORA-NICERF-V1-PadNC)") (class "Default")
      (node (ref "LORA-NICERF-V1") (pin "NC") (pinfunction "NC_NC") (pintype "bidirectional"))
    )
    (net (code "80") (name "unconnected-(LORA-NICERF-V1-PadNC1)") (class "Default")
      (node (ref "LORA-NICERF-V1") (pin "NC1") (pinfunction "NC1_NC1") (pintype "bidirectional"))
    )
    (net (code "81") (name "unconnected-(MD1-CLK-Pad20)") (class "Default")
      (node (ref "MD1") (pin "20") (pinfunction "CLK_20") (pintype "bidirectional"))
    )
    (net (code "82") (name "unconnected-(MD1-CMD-Pad19)") (class "Default")
      (node (ref "MD1") (pin "19") (pinfunction "CMD_19") (pintype "bidirectional"))
    )
    (net (code "83") (name "unconnected-(MD1-IO2-Pad24)") (class "Default")
      (node (ref "MD1") (pin "24") (pinfunction "IO2_24") (pintype "bidirectional"))
    )
    (net (code "84") (name "unconnected-(MD1-IO12-Pad14)") (class "Default")
      (node (ref "MD1") (pin "14") (pinfunction "IO12_14") (pintype "bidirectional"))
    )
    (net (code "85") (name "unconnected-(MD1-IO13-Pad16)") (class "Default")
      (node (ref "MD1") (pin "16") (pinfunction "IO13_16") (pintype "bidirectional"))
    )
    (net (code "86") (name "unconnected-(MD1-IO34-Pad6)") (class "Default")
      (node (ref "MD1") (pin "6") (pinfunction "IO34_6") (pintype "bidirectional"))
    )
    (net (code "87") (name "unconnected-(MD1-IO35-Pad7)") (class "Default")
      (node (ref "MD1") (pin "7") (pinfunction "IO35_7") (pintype "bidirectional"))
    )
    (net (code "88") (name "unconnected-(MD1-NC-Pad32)") (class "Default")
      (node (ref "MD1") (pin "32") (pinfunction "NC_32") (pintype "passive"))
    )
    (net (code "89") (name "unconnected-(MD1-SD0-Pad21)") (class "Default")
      (node (ref "MD1") (pin "21") (pinfunction "SD0_21") (pintype "bidirectional"))
    )
    (net (code "90") (name "unconnected-(MD1-SD1-Pad22)") (class "Default")
      (node (ref "MD1") (pin "22") (pinfunction "SD1_22") (pintype "bidirectional"))
    )
    (net (code "91") (name "unconnected-(MD1-SD2-Pad17)") (class "Default")
      (node (ref "MD1") (pin "17") (pinfunction "SD2_17") (pintype "bidirectional"))
    )
    (net (code "92") (name "unconnected-(MD1-SD3-Pad18)") (class "Default")
      (node (ref "MD1") (pin "18") (pinfunction "SD3_18") (pintype "bidirectional"))
    )
    (net (code "93") (name "unconnected-(MD1-SENSOR_VN-Pad5)") (class "Default")
      (node (ref "MD1") (pin "5") (pinfunction "SENSOR_VN_5") (pintype "input"))
    )
    (net (code "94") (name "unconnected-(MD1-SENSOR_VP-Pad4)") (class "Default")
      (node (ref "MD1") (pin "4") (pinfunction "SENSOR_VP_4") (pintype "input"))
    )
    (net (code "95") (name "unconnected-(U$2-CTS-Pad9)") (class "Default")
      (node (ref "U$2") (pin "9") (pinfunction "CTS_9") (pintype "bidirectional"))
    )
    (net (code "96") (name "unconnected-(U$2-DCD-Pad12)") (class "Default")
      (node (ref "U$2") (pin "12") (pinfunction "DCD_12") (pintype "bidirectional"))
    )
    (net (code "97") (name "unconnected-(U$2-DSR-Pad10)") (class "Default")
      (node (ref "U$2") (pin "10") (pinfunction "DSR_10") (pintype "bidirectional"))
    )
    (net (code "98") (name "unconnected-(U$2-RI-Pad11)") (class "Default")
      (node (ref "U$2") (pin "11") (pinfunction "RI_11") (pintype "bidirectional"))
    )
    (net (code "99") (name "unconnected-(U$2-RS232-Pad15)") (class "Default")
      (node (ref "U$2") (pin "15") (pinfunction "RS232_15") (pintype "bidirectional"))
    )
    (net (code "100") (name "unconnected-(U1-BP-Pad4)") (class "Default")
      (node (ref "U1") (pin "4") (pinfunction "BP_4") (pintype "passive"))
    )
    (net (code "101") (name "unconnected-(U2-BP-Pad4)") (class "Default")
      (node (ref "U2") (pin "4") (pinfunction "BP_4") (pintype "passive"))
    )
  )
)
